# diybmsv4-00.net
KiCad netlist of a schematic drawn in EAGLE
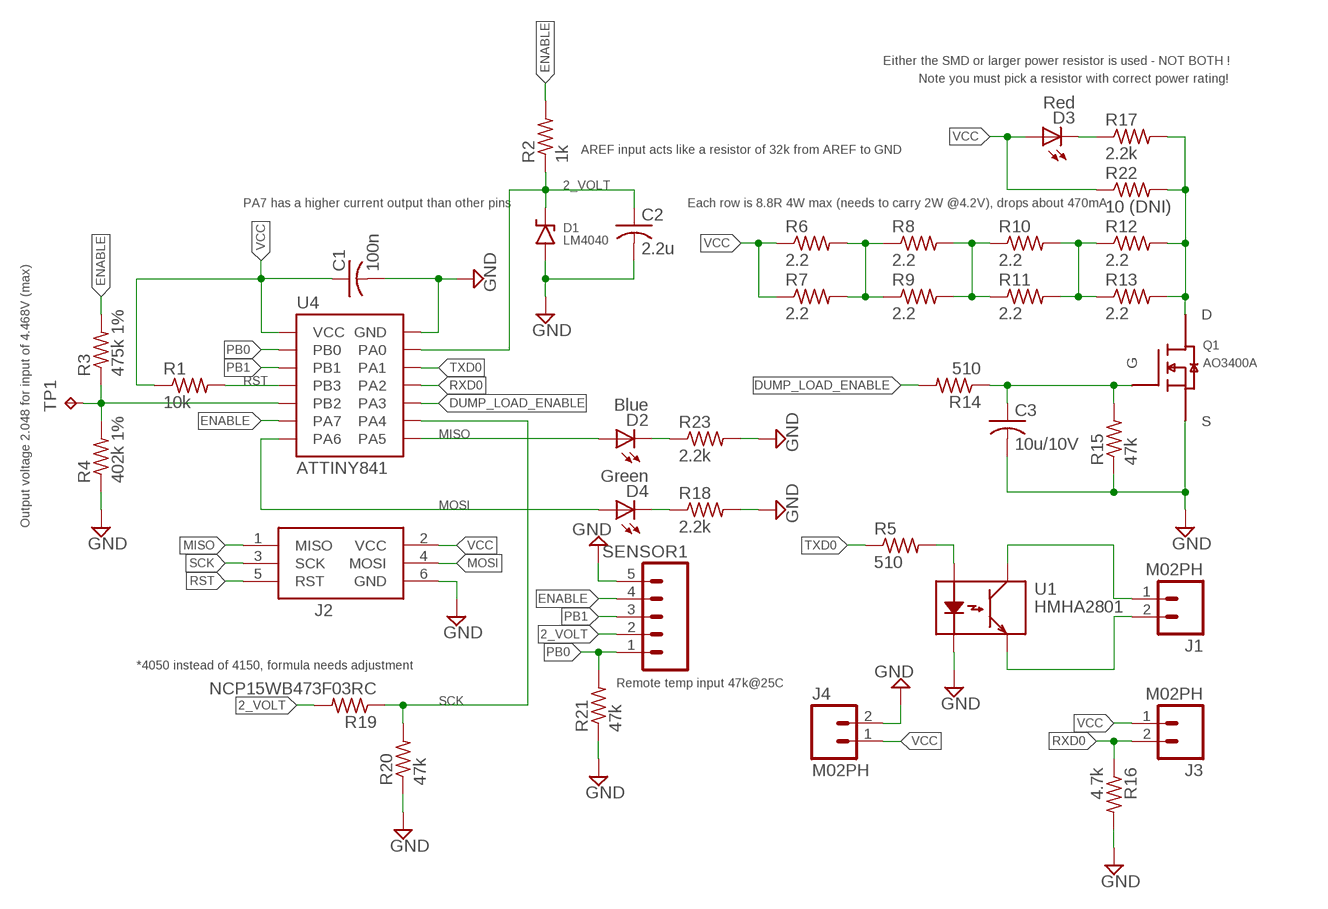
[diagram p0: schematic, sheet 1]

(export (version "E")
  (design (tool "Eeschema 10.0.6"))
  (components
    (comp (ref "C1")
      (value "100n")
      (footprint "eagle-import:C0402")
      (libsource (lib "eagle-import") (part "C-USC0402"))
    )
    (comp (ref "C2")
      (value "2.2u")
      (footprint "eagle-import:C0402")
      (libsource (lib "eagle-import") (part "C-USC0402"))
    )
    (comp (ref "C3")
      (value "10u/10V")
      (footprint "eagle-import:C0402")
      (libsource (lib "eagle-import") (part "C-USC0402"))
    )
    (comp (ref "D1")
      (value "LM4040")
      (footprint "eagle-import:SOT23")
      (libsource (lib "eagle-import") (part "LM4040"))
    )
    (comp (ref "D2")
      (value "Blue")
      (footprint "eagle-import:CHIPLED_0603")
      (libsource (lib "eagle-import") (part "LEDCHIPLED_0603"))
    )
    (comp (ref "D3")
      (value "Red")
      (footprint "eagle-import:CHIPLED_0603")
      (libsource (lib "eagle-import") (part "LEDCHIPLED_0603"))
    )
    (comp (ref "D4")
      (value "Green")
      (footprint "eagle-import:CHIPLED_0603")
      (libsource (lib "eagle-import") (part "LEDCHIPLED_0603"))
    )
    (comp (ref "J1")
      (value "M02PH")
      (footprint "eagle-import:S2B-PH-RA")
      (libsource (lib "eagle-import") (part "M02PH"))
    )
    (comp (ref "J2")
      (value "AVRISP-6")
      (footprint "eagle-import:AVRISP")
      (libsource (lib "eagle-import") (part "AVRISP-6"))
    )
    (comp (ref "J3")
      (value "M02PH")
      (footprint "eagle-import:S2B-PH-RA")
      (libsource (lib "eagle-import") (part "M02PH"))
    )
    (comp (ref "J4")
      (value "M02PH")
      (footprint "eagle-import:S2B-PH-RA")
      (libsource (lib "eagle-import") (part "M02PH"))
    )
    (comp (ref "Q1")
      (value "AO3400A")
      (footprint "eagle-import:SOT23")
      (libsource (lib "eagle-import") (part "AO3414"))
    )
    (comp (ref "R1")
      (value "10k")
      (footprint "eagle-import:R0402")
      (libsource (lib "eagle-import") (part "R-US_R0402"))
    )
    (comp (ref "R2")
      (value "1k")
      (footprint "eagle-import:R0402")
      (libsource (lib "eagle-import") (part "R-US_R0402"))
    )
    (comp (ref "R3")
      (value "475k 1%")
      (footprint "eagle-import:R0402")
      (libsource (lib "eagle-import") (part "R-US_R0402"))
    )
    (comp (ref "R4")
      (value "402k 1%")
      (footprint "eagle-import:R0402")
      (libsource (lib "eagle-import") (part "R-US_R0402"))
    )
    (comp (ref "R5")
      (value "510")
      (footprint "eagle-import:R0402")
      (libsource (lib "eagle-import") (part "R-US_R0402"))
    )
    (comp (ref "R6")
      (value "2.2")
      (footprint "eagle-import:R2512")
      (libsource (lib "eagle-import") (part "R-US_R2512"))
    )
    (comp (ref "R7")
      (value "2.2")
      (footprint "eagle-import:R2512")
      (libsource (lib "eagle-import") (part "R-US_R2512"))
    )
    (comp (ref "R8")
      (value "2.2")
      (footprint "eagle-import:R2512")
      (libsource (lib "eagle-import") (part "R-US_R2512"))
    )
    (comp (ref "R9")
      (value "2.2")
      (footprint "eagle-import:R2512")
      (libsource (lib "eagle-import") (part "R-US_R2512"))
    )
    (comp (ref "R10")
      (value "2.2")
      (footprint "eagle-import:R2512")
      (libsource (lib "eagle-import") (part "R-US_R2512"))
    )
    (comp (ref "R11")
      (value "2.2")
      (footprint "eagle-import:R2512")
      (libsource (lib "eagle-import") (part "R-US_R2512"))
    )
    (comp (ref "R12")
      (value "2.2")
      (footprint "eagle-import:R2512")
      (libsource (lib "eagle-import") (part "R-US_R2512"))
    )
    (comp (ref "R13")
      (value "2.2")
      (footprint "eagle-import:R2512")
      (libsource (lib "eagle-import") (part "R-US_R2512"))
    )
    (comp (ref "R14")
      (value "510")
      (footprint "eagle-import:R0402")
      (libsource (lib "eagle-import") (part "R-US_R0402"))
    )
    (comp (ref "R15")
      (value "47k")
      (footprint "eagle-import:R0402")
      (libsource (lib "eagle-import") (part "R-US_R0402"))
    )
    (comp (ref "R16")
      (value "4.7k")
      (footprint "eagle-import:R0402")
      (libsource (lib "eagle-import") (part "R-US_R0402"))
    )
    (comp (ref "R17")
      (value "2.2k")
      (footprint "eagle-import:R0402")
      (libsource (lib "eagle-import") (part "R-US_R0402"))
    )
    (comp (ref "R18")
      (value "2.2k")
      (footprint "eagle-import:R0402")
      (libsource (lib "eagle-import") (part "R-US_R0402"))
    )
    (comp (ref "R19")
      (value "NCP15WB473F03RC")
      (footprint "eagle-import:R0402")
      (libsource (lib "eagle-import") (part "R-US_R0402"))
    )
    (comp (ref "R20")
      (value "47k")
      (footprint "eagle-import:R0402")
      (libsource (lib "eagle-import") (part "R-US_R0402"))
    )
    (comp (ref "R21")
      (value "47k")
      (footprint "eagle-import:R0402")
      (libsource (lib "eagle-import") (part "R-US_R0402"))
    )
    (comp (ref "R22")
      (value "10 (DNI)")
      (footprint "eagle-import:R-5W-22X9P5X9P5")
      (libsource (lib "eagle-import") (part "RESISTOR25MM"))
    )
    (comp (ref "R23")
      (value "2.2k")
      (footprint "eagle-import:R0402")
      (libsource (lib "eagle-import") (part "R-US_R0402"))
    )
    (comp (ref "SENSOR1")
      (value "M05PTH")
      (footprint "eagle-import:1X05")
      (libsource (lib "eagle-import") (part "M05PTH"))
    )
    (comp (ref "TP1")
      (value "TPTP15SQ")
      (footprint "eagle-import:TP15SQ")
      (libsource (lib "eagle-import") (part "TPTP15SQ"))
    )
    (comp (ref "U1")
      (value "HMHA2801")
      (footprint "eagle-import:4-SOIC")
      (libsource (lib "eagle-import") (part "HMHA2801"))
    )
    (comp (ref "U4")
      (value "ATTINY841")
      (footprint "eagle-import:14-SOIC")
      (libsource (lib "eagle-import") (part "ATTINY841"))
    )
  )
  (nets
    (net (code "1") (name "2_VOLT") (class "Default")
      (node (ref "C2") (pin "1") (pinfunction "1_1") (pintype "passive"))
      (node (ref "D1") (pin "1") (pinfunction "K_1") (pintype "passive"))
      (node (ref "R19") (pin "2") (pinfunction "2_2") (pintype "passive"))
      (node (ref "R2") (pin "1") (pinfunction "1_1") (pintype "passive"))
      (node (ref "SENSOR1") (pin "2") (pinfunction "2_2") (pintype "passive"))
      (node (ref "U4") (pin "13") (pinfunction "PA0_13") (pintype "bidirectional"))
    )
    (net (code "2") (name "DUMP_LOAD_ENABLE") (class "Default")
      (node (ref "R14") (pin "2") (pinfunction "2_2") (pintype "passive"))
      (node (ref "U4") (pin "10") (pinfunction "PA3_10") (pintype "bidirectional"))
    )
    (net (code "3") (name "ENABLE") (class "Default")
      (node (ref "R2") (pin "2") (pinfunction "2_2") (pintype "passive"))
      (node (ref "R3") (pin "2") (pinfunction "2_2") (pintype "passive"))
      (node (ref "SENSOR1") (pin "4") (pinfunction "4_4") (pintype "passive"))
      (node (ref "U4") (pin "6") (pinfunction "PA7_6") (pintype "bidirectional"))
    )
    (net (code "4") (name "GND") (class "Default")
      (node (ref "C1") (pin "2") (pinfunction "2_2") (pintype "passive"))
      (node (ref "C2") (pin "2") (pinfunction "2_2") (pintype "passive"))
      (node (ref "C3") (pin "2") (pinfunction "2_2") (pintype "passive"))
      (node (ref "D1") (pin "2") (pinfunction "A_2") (pintype "passive"))
      (node (ref "J2") (pin "6") (pinfunction "GND_6") (pintype "power_in"))
      (node (ref "J4") (pin "2") (pinfunction "2_2") (pintype "passive"))
      (node (ref "Q1") (pin "2") (pinfunction "S_2") (pintype "bidirectional"))
      (node (ref "R15") (pin "1") (pinfunction "1_1") (pintype "passive"))
      (node (ref "R16") (pin "2") (pinfunction "2_2") (pintype "passive"))
      (node (ref "R18") (pin "2") (pinfunction "2_2") (pintype "passive"))
      (node (ref "R20") (pin "1") (pinfunction "1_1") (pintype "passive"))
      (node (ref "R21") (pin "1") (pinfunction "1_1") (pintype "passive"))
      (node (ref "R23") (pin "2") (pinfunction "2_2") (pintype "passive"))
      (node (ref "R4") (pin "1") (pinfunction "1_1") (pintype "passive"))
      (node (ref "SENSOR1") (pin "5") (pinfunction "5_5") (pintype "passive"))
      (node (ref "U1") (pin "2") (pinfunction "K_2") (pintype "bidirectional"))
      (node (ref "U4") (pin "14") (pinfunction "GND_14") (pintype "bidirectional"))
    )
    (net (code "5") (name "MISO") (class "Default")
      (node (ref "D2") (pin "A") (pinfunction "A_A") (pintype "passive"))
      (node (ref "J2") (pin "1") (pinfunction "MISO_1") (pintype "input"))
      (node (ref "U4") (pin "8") (pinfunction "PA5_8") (pintype "bidirectional"))
    )
    (net (code "6") (name "MOSI") (class "Default")
      (node (ref "D4") (pin "A") (pinfunction "A_A") (pintype "passive"))
      (node (ref "J2") (pin "4") (pinfunction "MOSI_4") (pintype "output"))
      (node (ref "U4") (pin "7") (pinfunction "PA6_7") (pintype "bidirectional"))
    )
    (net (code "7") (name "Net-(D2-PadC)") (class "Default")
      (node (ref "D2") (pin "C") (pinfunction "C_C") (pintype "passive"))
      (node (ref "R23") (pin "1") (pinfunction "1_1") (pintype "passive"))
    )
    (net (code "8") (name "Net-(D3-PadC)") (class "Default")
      (node (ref "D3") (pin "C") (pinfunction "C_C") (pintype "passive"))
      (node (ref "R17") (pin "1") (pinfunction "1_1") (pintype "passive"))
    )
    (net (code "9") (name "Net-(D4-PadC)") (class "Default")
      (node (ref "D4") (pin "C") (pinfunction "C_C") (pintype "passive"))
      (node (ref "R18") (pin "1") (pinfunction "1_1") (pintype "passive"))
    )
    (net (code "10") (name "Net-(Q1-D)") (class "Default")
      (node (ref "Q1") (pin "3") (pinfunction "D_3") (pintype "bidirectional"))
      (node (ref "R12") (pin "2") (pinfunction "2_2") (pintype "passive"))
      (node (ref "R13") (pin "2") (pinfunction "2_2") (pintype "passive"))
      (node (ref "R17") (pin "2") (pinfunction "2_2") (pintype "passive"))
      (node (ref "R22") (pin "2") (pinfunction "2_2") (pintype "passive"))
    )
    (net (code "11") (name "Net-(Q1-G)") (class "Default")
      (node (ref "C3") (pin "1") (pinfunction "1_1") (pintype "passive"))
      (node (ref "Q1") (pin "1") (pinfunction "G_1") (pintype "bidirectional"))
      (node (ref "R14") (pin "1") (pinfunction "1_1") (pintype "passive"))
      (node (ref "R15") (pin "2") (pinfunction "2_2") (pintype "passive"))
    )
    (net (code "12") (name "Net-(R6-Pad2)") (class "Default")
      (node (ref "R6") (pin "2") (pinfunction "2_2") (pintype "passive"))
      (node (ref "R7") (pin "2") (pinfunction "2_2") (pintype "passive"))
      (node (ref "R8") (pin "1") (pinfunction "1_1") (pintype "passive"))
      (node (ref "R9") (pin "1") (pinfunction "1_1") (pintype "passive"))
    )
    (net (code "13") (name "Net-(R10-Pad1)") (class "Default")
      (node (ref "R10") (pin "1") (pinfunction "1_1") (pintype "passive"))
      (node (ref "R11") (pin "1") (pinfunction "1_1") (pintype "passive"))
      (node (ref "R8") (pin "2") (pinfunction "2_2") (pintype "passive"))
      (node (ref "R9") (pin "2") (pinfunction "2_2") (pintype "passive"))
    )
    (net (code "14") (name "Net-(R10-Pad2)") (class "Default")
      (node (ref "R10") (pin "2") (pinfunction "2_2") (pintype "passive"))
      (node (ref "R11") (pin "2") (pinfunction "2_2") (pintype "passive"))
      (node (ref "R12") (pin "1") (pinfunction "1_1") (pintype "passive"))
      (node (ref "R13") (pin "1") (pinfunction "1_1") (pintype "passive"))
    )
    (net (code "15") (name "Net-(U1-A)") (class "Default")
      (node (ref "R5") (pin "2") (pinfunction "2_2") (pintype "passive"))
      (node (ref "U1") (pin "1") (pinfunction "A_1") (pintype "bidirectional"))
    )
    (net (code "16") (name "Net-(U1-C)") (class "Default")
      (node (ref "J1") (pin "1") (pinfunction "1_1") (pintype "passive"))
      (node (ref "U1") (pin "4") (pinfunction "C_4") (pintype "bidirectional"))
    )
    (net (code "17") (name "Net-(U1-E)") (class "Default")
      (node (ref "J1") (pin "2") (pinfunction "2_2") (pintype "passive"))
      (node (ref "U1") (pin "3") (pinfunction "E_3") (pintype "bidirectional"))
    )
    (net (code "18") (name "Net-(U4-PB2)") (class "Default")
      (node (ref "R3") (pin "1") (pinfunction "1_1") (pintype "passive"))
      (node (ref "R4") (pin "2") (pinfunction "2_2") (pintype "passive"))
      (node (ref "TP1") (pin "TP") (pinfunction "TP_TP") (pintype "input"))
      (node (ref "U4") (pin "5") (pinfunction "PB2_5") (pintype "bidirectional"))
    )
    (net (code "19") (name "PB0") (class "Default")
      (node (ref "R21") (pin "2") (pinfunction "2_2") (pintype "passive"))
      (node (ref "SENSOR1") (pin "1") (pinfunction "1_1") (pintype "passive"))
      (node (ref "U4") (pin "2") (pinfunction "PB0_2") (pintype "bidirectional"))
    )
    (net (code "20") (name "PB1") (class "Default")
      (node (ref "SENSOR1") (pin "3") (pinfunction "3_3") (pintype "passive"))
      (node (ref "U4") (pin "3") (pinfunction "PB1_3") (pintype "bidirectional"))
    )
    (net (code "21") (name "RST") (class "Default")
      (node (ref "J2") (pin "5") (pinfunction "RST_5") (pintype "output"))
      (node (ref "R1") (pin "2") (pinfunction "2_2") (pintype "passive"))
      (node (ref "U4") (pin "4") (pinfunction "PB3_4") (pintype "bidirectional"))
    )
    (net (code "22") (name "RXD0") (class "Default")
      (node (ref "J3") (pin "2") (pinfunction "2_2") (pintype "passive"))
      (node (ref "R16") (pin "1") (pinfunction "1_1") (pintype "passive"))
      (node (ref "U4") (pin "11") (pinfunction "PA2_11") (pintype "bidirectional"))
    )
    (net (code "23") (name "SCK") (class "Default")
      (node (ref "J2") (pin "3") (pinfunction "SCK_3") (pintype "output"))
      (node (ref "R19") (pin "1") (pinfunction "1_1") (pintype "passive"))
      (node (ref "R20") (pin "2") (pinfunction "2_2") (pintype "passive"))
      (node (ref "U4") (pin "9") (pinfunction "PA4_9") (pintype "bidirectional"))
    )
    (net (code "24") (name "TXD0") (class "Default")
      (node (ref "R5") (pin "1") (pinfunction "1_1") (pintype "passive"))
      (node (ref "U4") (pin "12") (pinfunction "PA1_12") (pintype "bidirectional"))
    )
    (net (code "25") (name "VCC") (class "Default")
      (node (ref "C1") (pin "1") (pinfunction "1_1") (pintype "passive"))
      (node (ref "D3") (pin "A") (pinfunction "A_A") (pintype "passive"))
      (node (ref "J2") (pin "2") (pinfunction "VCC_2") (pintype "power_in"))
      (node (ref "J3") (pin "1") (pinfunction "1_1") (pintype "passive"))
      (node (ref "J4") (pin "1") (pinfunction "1_1") (pintype "passive"))
      (node (ref "R1") (pin "1") (pinfunction "1_1") (pintype "passive"))
      (node (ref "R22") (pin "1") (pinfunction "1_1") (pintype "passive"))
      (node (ref "R6") (pin "1") (pinfunction "1_1") (pintype "passive"))
      (node (ref "R7") (pin "1") (pinfunction "1_1") (pintype "passive"))
      (node (ref "U4") (pin "1") (pinfunction "VCC_1") (pintype "bidirectional"))
    )
  )
)
